# Gas_sensor.net
KiCad netlist of a schematic drawn in Altium Designer
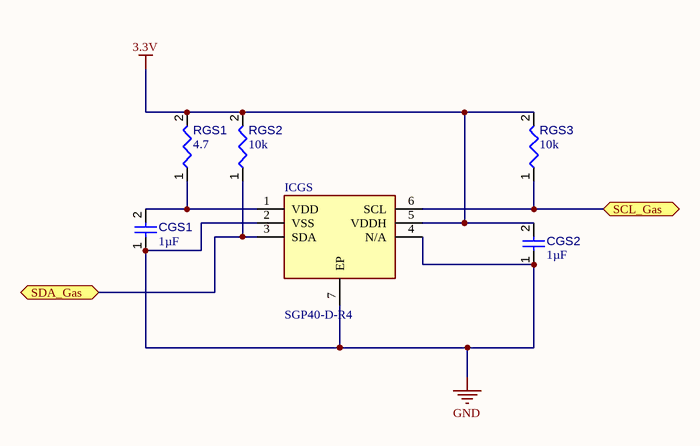
[diagram p0: Gas sensor.SchDoc]

(export (version "E")
  (design (tool "Eeschema 10.0.6"))
  (components
    (comp (ref "CGS1")
      (value "1µF")
      (footprint "CAPC1005X55X25ML5T10")
      (description "Chip Capacitor, 1 uF, +/- 10%, 6.3 V, 1005 (0402 Metric)")
      (fields (field (name "TOLERANCE") "10%") (field (name "Comment") "Capacitor 1 uF +/- 10% 6.3 V 1005"))
      (libsource (lib "Project Sunsat") (part "CAP-NP-2"))
    )
    (comp (ref "CGS2")
      (value "1µF")
      (footprint "CAPC1005X55X25ML5T10")
      (description "Chip Capacitor, 1 uF, +/- 10%, 6.3 V, 1005 (0402 Metric)")
      (fields (field (name "TOLERANCE") "10%") (field (name "Comment") "Capacitor 1 uF +/- 10% 6.3 V 1005"))
      (libsource (lib "Project Sunsat") (part "CAP-NP-2"))
    )
    (comp (ref "ICGS")
      (value "SGP40-D-R4")
      (footprint "SamacSys:SON80P244X244X95-7N")
      (description "Integrated Circuit")
      (fields (field (name "MOUSER PART NUMBER") "403-SGP40-D-R4"))
      (libsource (lib "*") (part "SGP40-D-R4"))
    )
    (comp (ref "RGS1")
      (value "4.7")
      (footprint "RESC0805(2012)_L")
      (description "Chip Resistor, 4,7 Ohms, +/-5 %, 125 mW, -55 to 155 degC, 0805")
      (fields (field (name "TOLERANCE") "5%") (field (name "POWER") "125mW"))
      (libsource (lib "Project Sunsat") (part "RES-2"))
    )
    (comp (ref "RGS2")
      (value "10k")
      (footprint "RESC0402(1005)_L")
      (description "Chip Resistor, 10 kOhms, +/-1 %, 63 mW, -55 to 125 degC, 0402")
      (fields (field (name "POWER") "63mW") (field (name "TOLERANCE") "1%"))
      (libsource (lib "Project Sunsat") (part "RES-2"))
    )
    (comp (ref "RGS3")
      (value "10k")
      (footprint "RESC0402(1005)_L")
      (description "Chip Resistor, 10 kOhms, +/-1 %, 63 mW, -55 to 125 degC, 0402")
      (fields (field (name "POWER") "63mW") (field (name "TOLERANCE") "1%"))
      (libsource (lib "Project Sunsat") (part "RES-2"))
    )
  )
  (nets
    (net (code "1") (name "/SCL_Gas") (class "Default")
      (node (ref "ICGS") (pin "6") (pinfunction "SCL_6") (pintype "passive"))
      (node (ref "RGS3") (pin "1") (pinfunction "1_1") (pintype "passive"))
    )
    (net (code "2") (name "/SDA_Gas") (class "Default")
      (node (ref "ICGS") (pin "3") (pinfunction "SDA_3") (pintype "passive"))
      (node (ref "RGS2") (pin "1") (pinfunction "1_1") (pintype "passive"))
    )
    (net (code "3") (name "3.3V") (class "Default")
      (node (ref "CGS2") (pin "2") (pinfunction "2_2") (pintype "passive"))
      (node (ref "ICGS") (pin "5") (pinfunction "VDDH_5") (pintype "passive"))
      (node (ref "RGS1") (pin "2") (pinfunction "2_2") (pintype "passive"))
      (node (ref "RGS2") (pin "2") (pinfunction "2_2") (pintype "passive"))
      (node (ref "RGS3") (pin "2") (pinfunction "2_2") (pintype "passive"))
    )
    (net (code "4") (name "GND") (class "Default")
      (node (ref "CGS1") (pin "1") (pinfunction "1_1") (pintype "passive"))
      (node (ref "CGS2") (pin "1") (pinfunction "1_1") (pintype "passive"))
      (node (ref "ICGS") (pin "2") (pinfunction "VSS_2") (pintype "passive"))
      (node (ref "ICGS") (pin "4") (pinfunction "N/A_4") (pintype "passive"))
      (node (ref "ICGS") (pin "7") (pinfunction "EP_7") (pintype "passive"))
    )
    (net (code "5") (name "Net-(ICGS-VDD)") (class "Default")
      (node (ref "CGS1") (pin "2") (pinfunction "2_2") (pintype "passive"))
      (node (ref "ICGS") (pin "1") (pinfunction "VDD_1") (pintype "passive"))
      (node (ref "RGS1") (pin "1") (pinfunction "1_1") (pintype "passive"))
    )
  )
)
